# Pwoer_module.net
KiCad netlist of a schematic drawn in Altium Designer
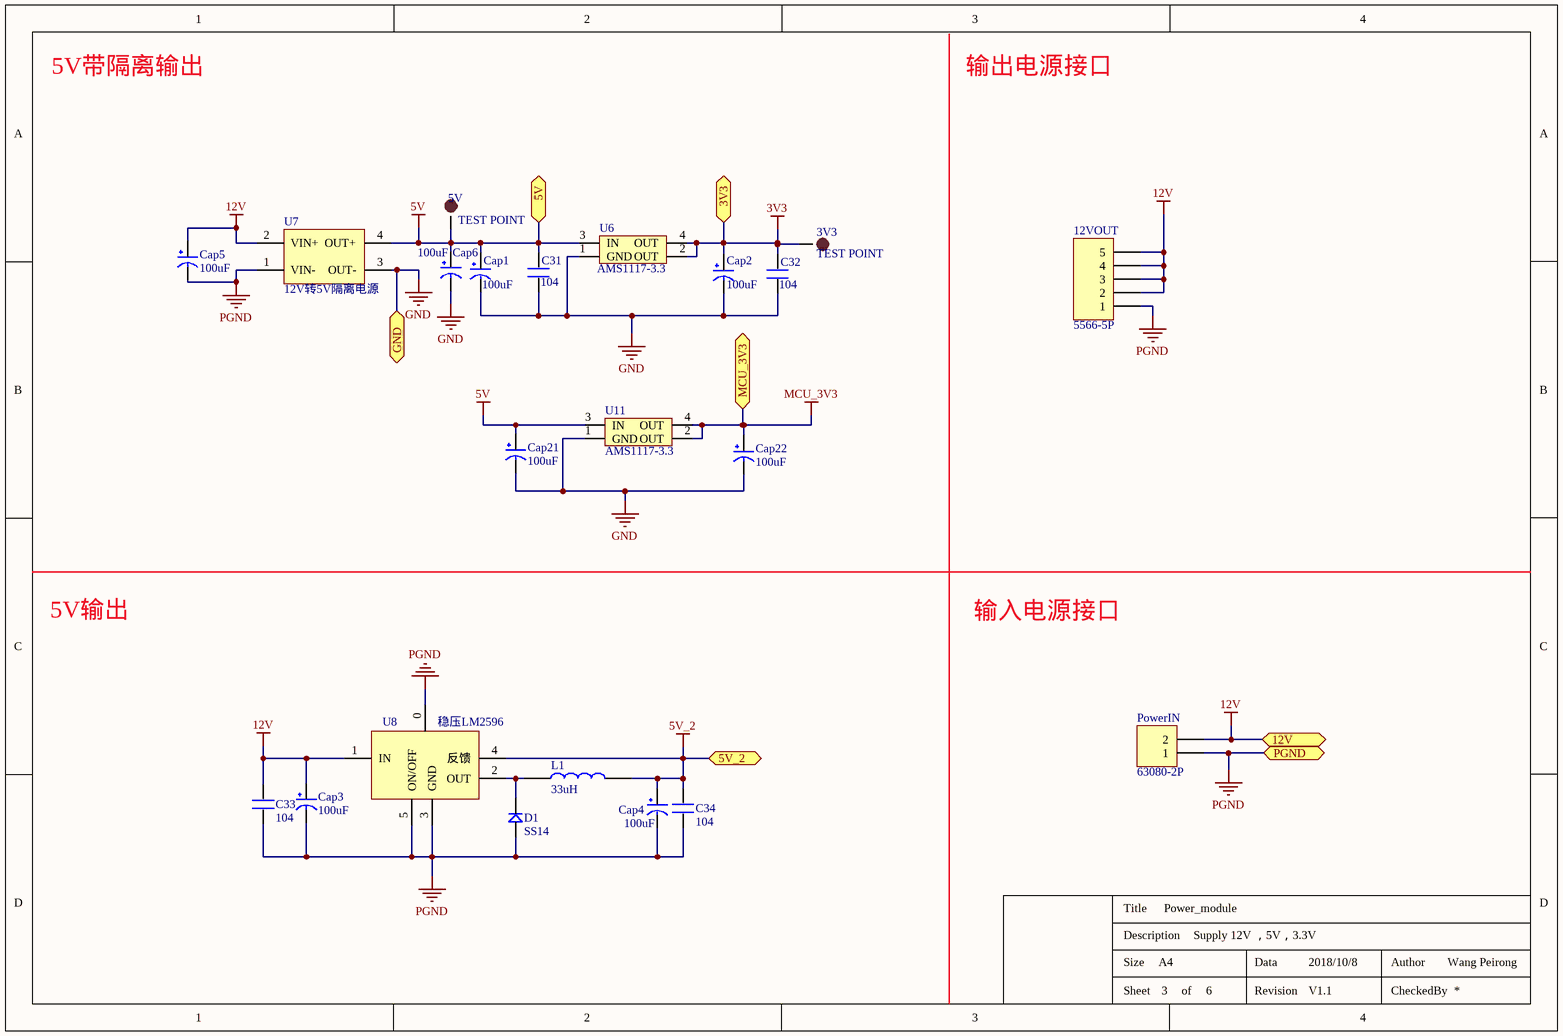
[diagram p0: Pwoer_module.SchDoc]

(export (version "E")
  (design (tool "Eeschema 10.0.6"))
  (components
    (comp (ref "3V3")
      (value "TEST POINT")
      (footprint "TP-1.5")
      (description "测试点")
      (libsource (lib "STM32F429核心板封装库") (part "TEST-POINT"))
    )
    (comp (ref "5V")
      (value "TEST POINT")
      (footprint "TP-1.5")
      (description "测试点")
      (libsource (lib "STM32F429核心板封装库") (part "TEST-POINT"))
    )
    (comp (ref "12VOUT")
      (value "5566-5P")
      (footprint "5566-5P")
      (description "Header, 5-Pin")
      (fields (field (name "PUBLISHER") "Altium Limited"))
      (libsource (lib "接插件集成库") (part "Header 5"))
    )
    (comp (ref "C31") (value "104") (footprint "0603P") (libsource (lib "阿波罗STM32F4&F7底板封装库") (part "C")))
    (comp (ref "C32") (value "104") (footprint "0603P") (libsource (lib "阿波罗STM32F4&F7底板封装库") (part "C")))
    (comp (ref "C33") (value "104") (footprint "0603P") (libsource (lib "阿波罗STM32F4&F7底板封装库") (part "C")))
    (comp (ref "C34") (value "104") (footprint "0603P") (libsource (lib "阿波罗STM32F4&F7底板封装库") (part "C")))
    (comp (ref "Cap1")
      (value "100uF")
      (footprint "CC6.56.5")
      (libsource (lib "阿波罗STM32F4&F7底板封装库") (part "CAP"))
    )
    (comp (ref "Cap2")
      (value "100uF")
      (footprint "CC6.56.5")
      (libsource (lib "阿波罗STM32F4&F7底板封装库") (part "CAP"))
    )
    (comp (ref "Cap3")
      (value "100uF")
      (footprint "CC6.56.5")
      (libsource (lib "阿波罗STM32F4&F7底板封装库") (part "CAP"))
    )
    (comp (ref "Cap4")
      (value "100uF")
      (footprint "CC6.56.5")
      (libsource (lib "阿波罗STM32F4&F7底板封装库") (part "CAP"))
    )
    (comp (ref "Cap5")
      (value "100uF")
      (footprint "CC6.56.5")
      (libsource (lib "阿波罗STM32F4&F7底板封装库") (part "CAP"))
    )
    (comp (ref "Cap6")
      (value "100uF")
      (footprint "CC6.56.5")
      (libsource (lib "阿波罗STM32F4&F7底板封装库") (part "CAP"))
    )
    (comp (ref "Cap21")
      (value "100uF")
      (footprint "CC6.56.5")
      (libsource (lib "阿波罗STM32F4&F7底板封装库") (part "CAP"))
    )
    (comp (ref "Cap22")
      (value "100uF")
      (footprint "CC6.56.5")
      (libsource (lib "阿波罗STM32F4&F7底板封装库") (part "CAP"))
    )
    (comp (ref "D1") (value "SS14") (footprint "DIODE_SOP") (libsource (lib "阿波罗STM32F4&F7底板封装库") (part "D")))
    (comp (ref "L1")
      (value "33uH")
      (footprint "电感-10*10")
      (description "Adjustable Inductor")
      (fields (field (name "Comment") "6电感") (field (name "PUBLISHER") "Altium Limited"))
      (libsource (lib "常用元件集成库") (part "6电感"))
    )
    (comp (ref "PowerIN")
      (value "63080-2P")
      (footprint "63038-2P")
      (description "Header, 2-Pin")
      (fields (field (name "PUBLISHER") "Altium Limited"))
      (libsource (lib "接插件集成库") (part "Header 2"))
    )
    (comp (ref "U6")
      (value "AMS1117-3.3")
      (footprint "AMS1117")
      (libsource (lib "阿波罗STM32F4&F7底板封装库") (part "AMS1117"))
    )
    (comp (ref "U7")
      (value "12V转5V隔离电源")
      (footprint "WRB1205MH")
      (libsource (lib "常用元件集成库") (part "12V转5V隔离电源"))
    )
    (comp (ref "U8") (value "稳压LM2596") (footprint "TO-263-5") (libsource (lib "IC原理图库") (part "稳压LM2596")))
    (comp (ref "U11")
      (value "AMS1117-3.3")
      (footprint "AMS1117")
      (libsource (lib "阿波罗STM32F4&F7底板封装库") (part "AMS1117"))
    )
  )
  (nets
    (net (code "1") (name "3V3") (class "Default")
      (node (ref "3V3") (pin "1") (pinfunction "1_1") (pintype "passive"))
      (node (ref "C32") (pin "2") (pintype "passive"))
      (node (ref "Cap2") (pin "1") (pinfunction "VCC_1") (pintype "passive"))
      (node (ref "U6") (pin "2") (pinfunction "OUT_2") (pintype "passive"))
      (node (ref "U6") (pin "4") (pinfunction "OUT_4") (pintype "passive"))
    )
    (net (code "2") (name "5V") (class "Default")
      (node (ref "5V") (pin "1") (pinfunction "1_1") (pintype "passive"))
      (node (ref "C31") (pin "2") (pintype "passive"))
      (node (ref "Cap1") (pin "1") (pinfunction "VCC_1") (pintype "passive"))
      (node (ref "Cap21") (pin "1") (pinfunction "VCC_1") (pintype "passive"))
      (node (ref "Cap6") (pin "1") (pinfunction "VCC_1") (pintype "passive"))
      (node (ref "U11") (pin "3") (pinfunction "IN_3") (pintype "passive"))
      (node (ref "U6") (pin "3") (pinfunction "IN_3") (pintype "passive"))
      (node (ref "U7") (pin "4") (pinfunction "OUT+_4") (pintype "passive"))
    )
    (net (code "3") (name "5V_2") (class "Default")
      (node (ref "C34") (pin "2") (pintype "passive"))
      (node (ref "Cap4") (pin "1") (pinfunction "VCC_1") (pintype "passive"))
      (node (ref "L1") (pin "2") (pinfunction "2_2") (pintype "passive"))
      (node (ref "U8") (pin "4") (pinfunction "反馈_4") (pintype "passive"))
    )
    (net (code "4") (name "12V") (class "Default")
      (node (ref "12VOUT") (pin "2") (pinfunction "2_2") (pintype "passive"))
      (node (ref "12VOUT") (pin "3") (pinfunction "3_3") (pintype "passive"))
      (node (ref "12VOUT") (pin "4") (pinfunction "4_4") (pintype "passive"))
      (node (ref "12VOUT") (pin "5") (pinfunction "5_5") (pintype "passive"))
      (node (ref "C33") (pin "2") (pintype "passive"))
      (node (ref "Cap3") (pin "1") (pinfunction "VCC_1") (pintype "passive"))
      (node (ref "Cap5") (pin "1") (pinfunction "VCC_1") (pintype "passive"))
      (node (ref "PowerIN") (pin "2") (pinfunction "2_2") (pintype "passive"))
      (node (ref "U7") (pin "2") (pinfunction "VIN+_2") (pintype "passive"))
      (node (ref "U8") (pin "1") (pinfunction "IN_1") (pintype "passive"))
    )
    (net (code "5") (name "GND") (class "Default")
      (node (ref "C31") (pin "1") (pintype "passive"))
      (node (ref "C32") (pin "1") (pintype "passive"))
      (node (ref "Cap1") (pin "2") (pinfunction "GND_2") (pintype "passive"))
      (node (ref "Cap2") (pin "2") (pinfunction "GND_2") (pintype "passive"))
      (node (ref "Cap21") (pin "2") (pinfunction "GND_2") (pintype "passive"))
      (node (ref "Cap22") (pin "2") (pinfunction "GND_2") (pintype "passive"))
      (node (ref "Cap6") (pin "2") (pinfunction "GND_2") (pintype "passive"))
      (node (ref "U11") (pin "1") (pinfunction "GND_1") (pintype "passive"))
      (node (ref "U6") (pin "1") (pinfunction "GND_1") (pintype "passive"))
      (node (ref "U7") (pin "3") (pinfunction "OUT-_3") (pintype "passive"))
    )
    (net (code "6") (name "MCU_3V3") (class "Default")
      (node (ref "Cap22") (pin "1") (pinfunction "VCC_1") (pintype "passive"))
      (node (ref "U11") (pin "2") (pinfunction "OUT_2") (pintype "passive"))
      (node (ref "U11") (pin "4") (pinfunction "OUT_4") (pintype "passive"))
    )
    (net (code "7") (name "Net-(U8-OUT)") (class "Default")
      (node (ref "D1") (pin "2") (pintype "passive"))
      (node (ref "L1") (pin "1") (pinfunction "1_1") (pintype "passive"))
      (node (ref "U8") (pin "2") (pinfunction "OUT_2") (pintype "passive"))
    )
    (net (code "8") (name "PGND") (class "Default")
      (node (ref "12VOUT") (pin "1") (pinfunction "1_1") (pintype "passive"))
      (node (ref "C33") (pin "1") (pintype "passive"))
      (node (ref "C34") (pin "1") (pintype "passive"))
      (node (ref "Cap3") (pin "2") (pinfunction "GND_2") (pintype "passive"))
      (node (ref "Cap4") (pin "2") (pinfunction "GND_2") (pintype "passive"))
      (node (ref "Cap5") (pin "2") (pinfunction "GND_2") (pintype "passive"))
      (node (ref "D1") (pin "1") (pintype "passive"))
      (node (ref "PowerIN") (pin "1") (pinfunction "1_1") (pintype "passive"))
      (node (ref "U7") (pin "1") (pinfunction "VIN-_1") (pintype "passive"))
      (node (ref "U8") (pin "0") (pinfunction "0_0") (pintype "passive"))
      (node (ref "U8") (pin "3") (pinfunction "GND_3") (pintype "passive"))
      (node (ref "U8") (pin "5") (pinfunction "ON/OFF_5") (pintype "passive"))
    )
  )
)
